# Sheet1.net
KiCad netlist of a schematic drawn in Altium Designer
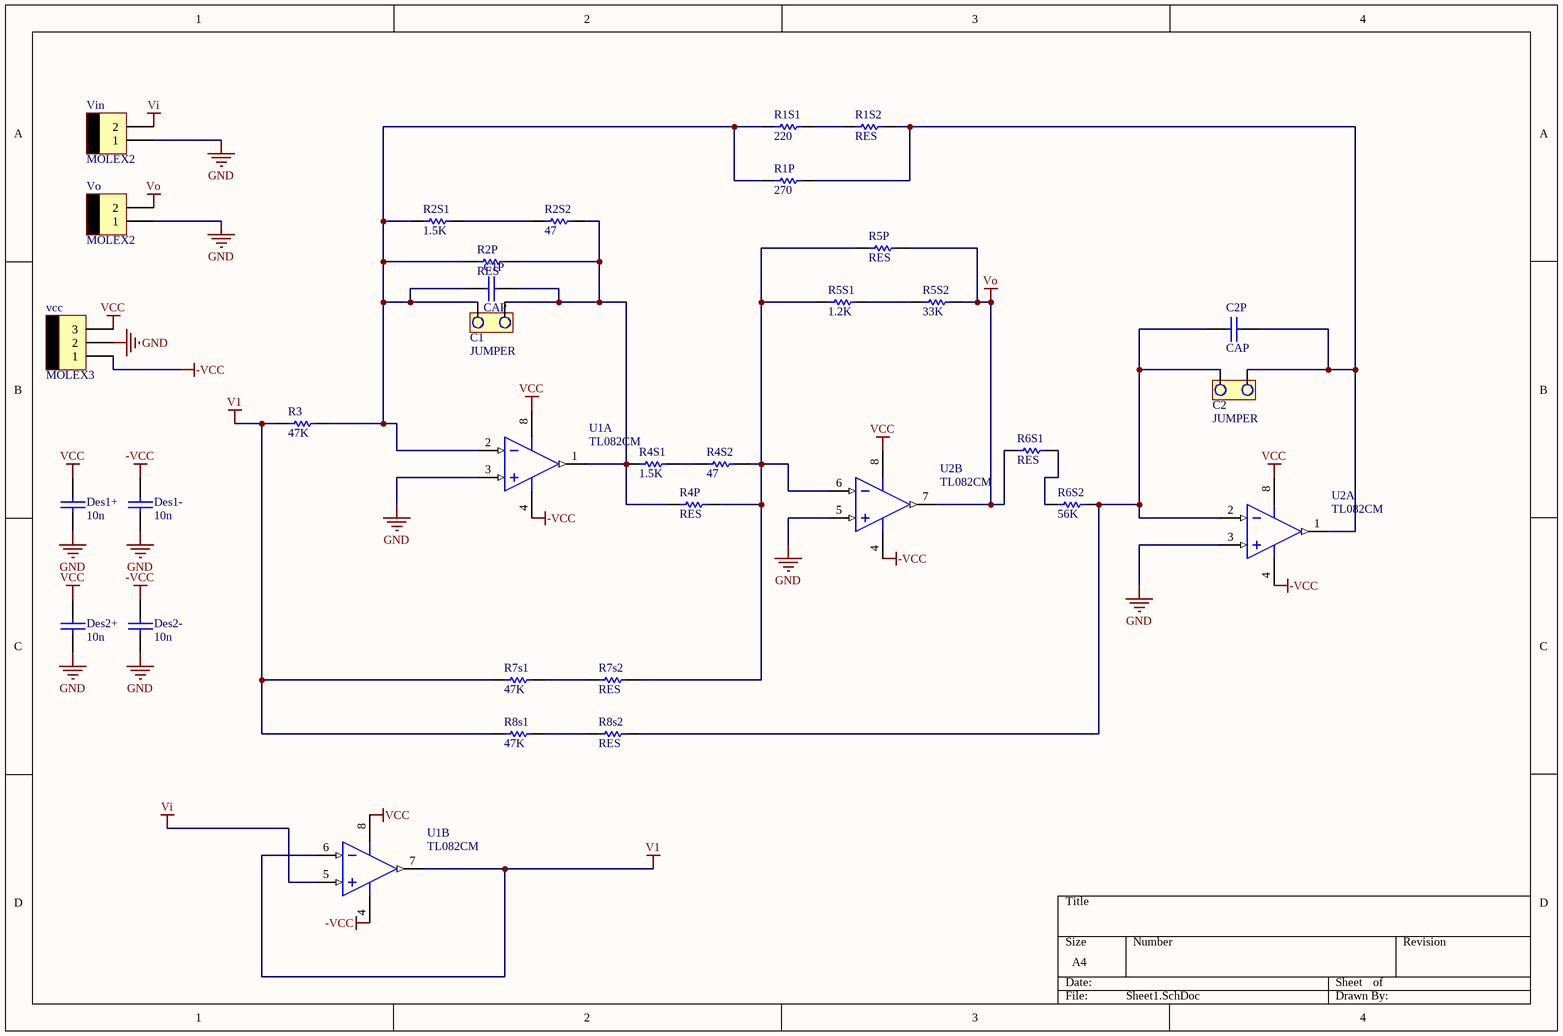
[diagram p0: Sheet1.SchDoc]

(export (version "E")
  (design (tool "Eeschema 10.0.6"))
  (components
    (comp (ref "C1") (value "JUMPER") (footprint "JUMPER2") (libsource (lib "LIBEBAL") (part "JUMPER")))
    (comp (ref "C1P") (value "CAP") (footprint "0805") (libsource (lib "LIB PIO IX") (part "CAP")))
    (comp (ref "C2") (value "JUMPER") (footprint "JUMPER2") (libsource (lib "LIBEBAL") (part "JUMPER")))
    (comp (ref "C2P") (value "CAP") (footprint "0805") (libsource (lib "LIB PIO IX") (part "CAP")))
    (comp (ref "Des1+") (value "10n") (footprint "0805") (libsource (lib "LIBEBAL") (part "CAP")))
    (comp (ref "Des1-") (value "10n") (footprint "0805") (libsource (lib "LIBEBAL") (part "CAP")))
    (comp (ref "Des2+") (value "10n") (footprint "0805") (libsource (lib "LIBEBAL") (part "CAP")))
    (comp (ref "Des2-") (value "10n") (footprint "0805") (libsource (lib "LIBEBAL") (part "CAP")))
    (comp (ref "R1P") (value "270") (footprint "0805") (libsource (lib "LIBEBAL") (part "RES")))
    (comp (ref "R1S1") (value "220") (footprint "0805") (libsource (lib "LIBEBAL") (part "RES")))
    (comp (ref "R1S2") (value "RES") (footprint "0805") (libsource (lib "LIB PIO IX") (part "RES")))
    (comp (ref "R2P") (value "RES") (footprint "0805") (libsource (lib "LIB PIO IX") (part "RES")))
    (comp (ref "R2S1") (value "1.5K") (footprint "0805") (libsource (lib "LIBEBAL") (part "RES")))
    (comp (ref "R2S2") (value "47") (footprint "0805") (libsource (lib "LIBEBAL") (part "RES")))
    (comp (ref "R3") (value "47K") (footprint "0805") (libsource (lib "LIBEBAL") (part "RES")))
    (comp (ref "R4P") (value "RES") (footprint "0805") (libsource (lib "LIB PIO IX") (part "RES")))
    (comp (ref "R4S1") (value "1.5K") (footprint "0805") (libsource (lib "LIBEBAL") (part "RES")))
    (comp (ref "R4S2") (value "47") (footprint "0805") (libsource (lib "LIBEBAL") (part "RES")))
    (comp (ref "R5P") (value "RES") (footprint "0805") (libsource (lib "LIB PIO IX") (part "RES")))
    (comp (ref "R5S1") (value "1.2K") (footprint "0805") (libsource (lib "LIBEBAL") (part "RES")))
    (comp (ref "R5S2") (value "33K") (footprint "0805") (libsource (lib "LIBEBAL") (part "RES")))
    (comp (ref "R6S1") (value "RES") (footprint "0805") (libsource (lib "LIB PIO IX") (part "RES")))
    (comp (ref "R6S2") (value "56K") (footprint "0805") (libsource (lib "LIBEBAL") (part "RES")))
    (comp (ref "R7s1") (value "47K") (footprint "0805") (libsource (lib "LIBEBAL") (part "RES")))
    (comp (ref "R7s2") (value "RES") (footprint "0805") (libsource (lib "LIB PIO IX") (part "RES")))
    (comp (ref "R8s1") (value "47K") (footprint "0805") (libsource (lib "LIBEBAL") (part "RES")))
    (comp (ref "R8s2") (value "RES") (footprint "0805") (libsource (lib "LIB PIO IX") (part "RES")))
    (comp (ref "U1")
      (value "TL082CM")
      (footprint "M08A_N")
      (description "Wide Bandwidth Dual JFET Input Operational Amplifier, 8-pin Narrow SOIC")
      (fields
        (field (name "MANUFACTURER") "National Semiconductor")
        (field (name "PUBLISHER") "Altium Limited")
      )
      (libsource (lib "NSC Amplifier") (part "TL082CM"))
    )
    (comp (ref "U2")
      (value "TL082CM")
      (footprint "M08A_N")
      (description "Wide Bandwidth Dual JFET Input Operational Amplifier, 8-pin Narrow SOIC")
      (fields
        (field (name "MANUFACTURER") "National Semiconductor")
        (field (name "PUBLISHER") "Altium Limited")
      )
      (libsource (lib "NSC Amplifier") (part "TL082CM"))
    )
    (comp (ref "vcc") (value "MOLEX3") (footprint "MOLEX3") (libsource (lib "LIB PIO IX") (part "MOLEX3")))
    (comp (ref "Vin") (value "MOLEX2") (footprint "MOLEX2") (libsource (lib "LIB PIO IX") (part "MOLEX2")))
    (comp (ref "Vo") (value "MOLEX2") (footprint "MOLEX2") (libsource (lib "LIB PIO IX") (part "MOLEX2")))
  )
  (nets
    (net (code "1") (name "-VCC") (class "Default")
      (node (ref "Des1-") (pin "1") (pinfunction "1_1") (pintype "passive"))
      (node (ref "Des2-") (pin "1") (pinfunction "1_1") (pintype "passive"))
      (node (ref "U1") (pin "4") (pinfunction "V-_4") (pintype "power_in"))
      (node (ref "U2") (pin "4") (pinfunction "V-_4") (pintype "power_in"))
      (node (ref "vcc") (pin "1") (pinfunction "1_1") (pintype "passive"))
    )
    (net (code "2") (name "GND") (class "Default")
      (node (ref "Des1+") (pin "2") (pinfunction "2_2") (pintype "passive"))
      (node (ref "Des1-") (pin "2") (pinfunction "2_2") (pintype "passive"))
      (node (ref "Des2+") (pin "2") (pinfunction "2_2") (pintype "passive"))
      (node (ref "Des2-") (pin "2") (pinfunction "2_2") (pintype "passive"))
      (node (ref "U1") (pin "3") (pinfunction "INA+_3") (pintype "input"))
      (node (ref "U2") (pin "3") (pinfunction "INA+_3") (pintype "input"))
      (node (ref "U2") (pin "5") (pinfunction "INB+_5") (pintype "input"))
      (node (ref "Vin") (pin "1") (pinfunction "1_1") (pintype "passive"))
      (node (ref "Vo") (pin "1") (pinfunction "1_1") (pintype "passive"))
      (node (ref "vcc") (pin "2") (pinfunction "2_2") (pintype "passive"))
    )
    (net (code "3") (name "Net-(R1S1-Pad2)") (class "Default")
      (node (ref "R1S1") (pin "2") (pinfunction "2_2") (pintype "passive"))
      (node (ref "R1S2") (pin "1") (pinfunction "1_1") (pintype "passive"))
    )
    (net (code "4") (name "Net-(R2S1-Pad2)") (class "Default")
      (node (ref "R2S1") (pin "2") (pinfunction "2_2") (pintype "passive"))
      (node (ref "R2S2") (pin "1") (pinfunction "1_1") (pintype "passive"))
    )
    (net (code "5") (name "Net-(R4S1-Pad2)") (class "Default")
      (node (ref "R4S1") (pin "2") (pinfunction "2_2") (pintype "passive"))
      (node (ref "R4S2") (pin "1") (pinfunction "1_1") (pintype "passive"))
    )
    (net (code "6") (name "Net-(R5S1-Pad2)") (class "Default")
      (node (ref "R5S1") (pin "2") (pinfunction "2_2") (pintype "passive"))
      (node (ref "R5S2") (pin "1") (pinfunction "1_1") (pintype "passive"))
    )
    (net (code "7") (name "Net-(R6S1-Pad2)") (class "Default")
      (node (ref "R6S1") (pin "2") (pinfunction "2_2") (pintype "passive"))
      (node (ref "R6S2") (pin "1") (pinfunction "1_1") (pintype "passive"))
    )
    (net (code "8") (name "Net-(R7s1-Pad2)") (class "Default")
      (node (ref "R7s1") (pin "2") (pinfunction "2_2") (pintype "passive"))
      (node (ref "R7s2") (pin "1") (pinfunction "1_1") (pintype "passive"))
    )
    (net (code "9") (name "Net-(R8s1-Pad2)") (class "Default")
      (node (ref "R8s1") (pin "2") (pinfunction "2_2") (pintype "passive"))
      (node (ref "R8s2") (pin "1") (pinfunction "1_1") (pintype "passive"))
    )
    (net (code "10") (name "Net-(U1A-INA-)") (class "Default")
      (node (ref "C1") (pin "1") (pinfunction "1_1") (pintype "passive"))
      (node (ref "C1P") (pin "1") (pinfunction "1_1") (pintype "passive"))
      (node (ref "R1P") (pin "1") (pinfunction "1_1") (pintype "passive"))
      (node (ref "R1S1") (pin "1") (pinfunction "1_1") (pintype "passive"))
      (node (ref "R2P") (pin "1") (pinfunction "1_1") (pintype "passive"))
      (node (ref "R2S1") (pin "1") (pinfunction "1_1") (pintype "passive"))
      (node (ref "R3") (pin "2") (pinfunction "2_2") (pintype "passive"))
      (node (ref "U1") (pin "2") (pinfunction "INA-_2") (pintype "input"))
    )
    (net (code "11") (name "Net-(U1A-OUTA)") (class "Default")
      (node (ref "C1") (pin "2") (pinfunction "2_2") (pintype "passive"))
      (node (ref "C1P") (pin "2") (pinfunction "2_2") (pintype "passive"))
      (node (ref "R2P") (pin "2") (pinfunction "2_2") (pintype "passive"))
      (node (ref "R2S2") (pin "2") (pinfunction "2_2") (pintype "passive"))
      (node (ref "R4P") (pin "1") (pinfunction "1_1") (pintype "passive"))
      (node (ref "R4S1") (pin "1") (pinfunction "1_1") (pintype "passive"))
      (node (ref "U1") (pin "1") (pinfunction "OUTA_1") (pintype "output"))
    )
    (net (code "12") (name "Net-(U2A-INA-)") (class "Default")
      (node (ref "C2") (pin "1") (pinfunction "1_1") (pintype "passive"))
      (node (ref "C2P") (pin "1") (pinfunction "1_1") (pintype "passive"))
      (node (ref "R6S2") (pin "2") (pinfunction "2_2") (pintype "passive"))
      (node (ref "R8s2") (pin "2") (pinfunction "2_2") (pintype "passive"))
      (node (ref "U2") (pin "2") (pinfunction "INA-_2") (pintype "input"))
    )
    (net (code "13") (name "Net-(U2A-OUTA)") (class "Default")
      (node (ref "C2") (pin "2") (pinfunction "2_2") (pintype "passive"))
      (node (ref "C2P") (pin "2") (pinfunction "2_2") (pintype "passive"))
      (node (ref "R1P") (pin "2") (pinfunction "2_2") (pintype "passive"))
      (node (ref "R1S2") (pin "2") (pinfunction "2_2") (pintype "passive"))
      (node (ref "U2") (pin "1") (pinfunction "OUTA_1") (pintype "output"))
    )
    (net (code "14") (name "Net-(U2B-INB-)") (class "Default")
      (node (ref "R4P") (pin "2") (pinfunction "2_2") (pintype "passive"))
      (node (ref "R4S2") (pin "2") (pinfunction "2_2") (pintype "passive"))
      (node (ref "R5P") (pin "1") (pinfunction "1_1") (pintype "passive"))
      (node (ref "R5S1") (pin "1") (pinfunction "1_1") (pintype "passive"))
      (node (ref "R7s2") (pin "2") (pinfunction "2_2") (pintype "passive"))
      (node (ref "U2") (pin "6") (pinfunction "INB-_6") (pintype "input"))
    )
    (net (code "15") (name "V1") (class "Default")
      (node (ref "R3") (pin "1") (pinfunction "1_1") (pintype "passive"))
      (node (ref "R7s1") (pin "1") (pinfunction "1_1") (pintype "passive"))
      (node (ref "R8s1") (pin "1") (pinfunction "1_1") (pintype "passive"))
      (node (ref "U1") (pin "6") (pinfunction "INB-_6") (pintype "input"))
      (node (ref "U1") (pin "7") (pinfunction "OUTB_7") (pintype "output"))
    )
    (net (code "16") (name "VCC") (class "Default")
      (node (ref "Des1+") (pin "1") (pinfunction "1_1") (pintype "passive"))
      (node (ref "Des2+") (pin "1") (pinfunction "1_1") (pintype "passive"))
      (node (ref "U1") (pin "8") (pinfunction "V+_8") (pintype "power_in"))
      (node (ref "U2") (pin "8") (pinfunction "V+_8") (pintype "power_in"))
      (node (ref "vcc") (pin "3") (pinfunction "3_3") (pintype "passive"))
    )
    (net (code "17") (name "Vi") (class "Default")
      (node (ref "U1") (pin "5") (pinfunction "INB+_5") (pintype "input"))
      (node (ref "Vin") (pin "2") (pinfunction "2_2") (pintype "passive"))
    )
    (net (code "18") (name "Vo") (class "Default")
      (node (ref "R5P") (pin "2") (pinfunction "2_2") (pintype "passive"))
      (node (ref "R5S2") (pin "2") (pinfunction "2_2") (pintype "passive"))
      (node (ref "R6S1") (pin "1") (pinfunction "1_1") (pintype "passive"))
      (node (ref "U2") (pin "7") (pinfunction "OUTB_7") (pintype "output"))
      (node (ref "Vo") (pin "2") (pinfunction "2_2") (pintype "passive"))
    )
  )
)
